# Sheet1.net
KiCad netlist of a schematic drawn in Altium Designer
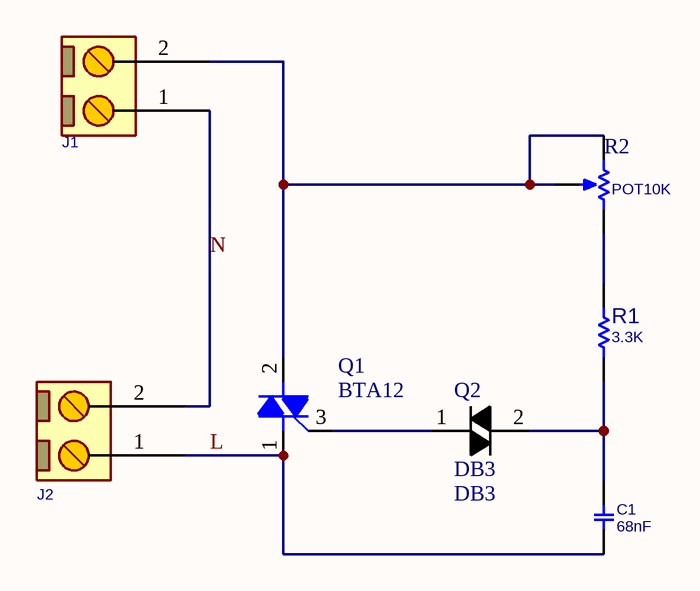
[diagram p0: Sheet1.SchDoc]

(export (version "E")
  (design (tool "Eeschema 10.0.6"))
  (components
    (comp (ref "C1")
      (value "68nF")
      (footprint "C_FLM_7X5H10")
      (description "CAP, FILM")
      (fields (field (name "MANF_P#") "MKS2C041001F00JA00") (field (name "MANF") "WIMA"))
      (libsource (lib "passive_thd") (part "CAP_THD_FLM_1uF_63v"))
    )
    (comp (ref "J1")
      (value "CONN_GMSTB2")
      (footprint "GMSTB762_2")
      (description "CONN, PHOENIX GMSTB, 7.62mm pitch")
      (fields (field (name "MANF_P#") "GMSTB 2,5/2-G-7,62"))
      (libsource (lib "conn_terminalB") (part "CONN_GMSTB762_2"))
    )
    (comp (ref "J2")
      (value "CONN_GMSTB2")
      (footprint "GMSTB762_2")
      (description "CONN, PHOENIX GMSTB, 7.62mm pitch")
      (fields (field (name "MANF_P#") "GMSTB 2,5/2-G-7,62"))
      (libsource (lib "conn_terminalB") (part "CONN_GMSTB762_2"))
    )
    (comp (ref "Q1")
      (value "BTA12")
      (footprint "TO220_3")
      (description "Triac, 600V, 12A, TO-220")
      (fields (field (name "MANF_P#") "BTA12-600BW, BTA12-600CW, BTA12-600TW") (field (name "MANF") "ST"))
      (libsource (lib "triac_diac") (part "TRIAC_BTA12-600_TO220"))
    )
    (comp (ref "Q2")
      (value "DB3")
      (footprint "D_AX03_DO35")
      (description "Diac, 32VBO, DO-35")
      (fields (field (name "MANF") "ST") (field (name "ALTIUM_VALUE") "DB3"))
      (libsource (lib "triac_diac") (part "DIAC_DB3_DO35"))
    )
    (comp (ref "R1")
      (value "3.3K")
      (footprint "R025W_AX04")
      (description "RESISTOR, THD")
      (fields (field (name "MANF_P#") "RK73H1ETTP4701F") (field (name "MANF") "KOA SPEER"))
      (libsource (lib "passive_thd") (part "RES_THD"))
    )
    (comp (ref "R2")
      (value "POT10K")
      (footprint "VOL_R")
      (description "RESISTOR, THD, Potentiometer Volume")
      (libsource (lib "resistor_pot_trimmer") (part "RES_THD_POT_VOL"))
    )
  )
  (nets
    (net (code "1") (name "/L") (class "Default")
      (node (ref "C1") (pin "1") (pinfunction "1_1") (pintype "passive"))
      (node (ref "J2") (pin "1") (pinfunction "1_1") (pintype "passive"))
      (node (ref "Q1") (pin "1") (pinfunction "T1_1") (pintype "passive"))
    )
    (net (code "2") (name "/N") (class "Default")
      (node (ref "J1") (pin "1") (pinfunction "1_1") (pintype "passive"))
      (node (ref "J2") (pin "2") (pinfunction "2_2") (pintype "passive"))
    )
    (net (code "3") (name "Net-(Q1-G)") (class "Default")
      (node (ref "Q1") (pin "3") (pinfunction "G_3") (pintype "passive"))
      (node (ref "Q2") (pin "1") (pinfunction "A1_1") (pintype "passive"))
    )
    (net (code "4") (name "Net-(Q1-T2)") (class "Default")
      (node (ref "J1") (pin "2") (pinfunction "2_2") (pintype "passive"))
      (node (ref "Q1") (pin "2") (pinfunction "T2_2") (pintype "passive"))
      (node (ref "R2") (pin "1") (pinfunction "TOP_1") (pintype "passive"))
      (node (ref "R2") (pin "2") (pinfunction "TAP_2") (pintype "passive"))
    )
    (net (code "5") (name "Net-(Q2-A2)") (class "Default")
      (node (ref "C1") (pin "2") (pinfunction "2_2") (pintype "passive"))
      (node (ref "Q2") (pin "2") (pinfunction "A2_2") (pintype "passive"))
      (node (ref "R1") (pin "2") (pinfunction "2_2") (pintype "passive"))
    )
    (net (code "6") (name "Net-(R2-BOT)") (class "Default")
      (node (ref "R1") (pin "1") (pinfunction "1_1") (pintype "passive"))
      (node (ref "R2") (pin "3") (pinfunction "BOT_3") (pintype "passive"))
    )
  )
)
